# TRHCO2_datalogger.net
KiCad netlist of a schematic drawn in EAGLE
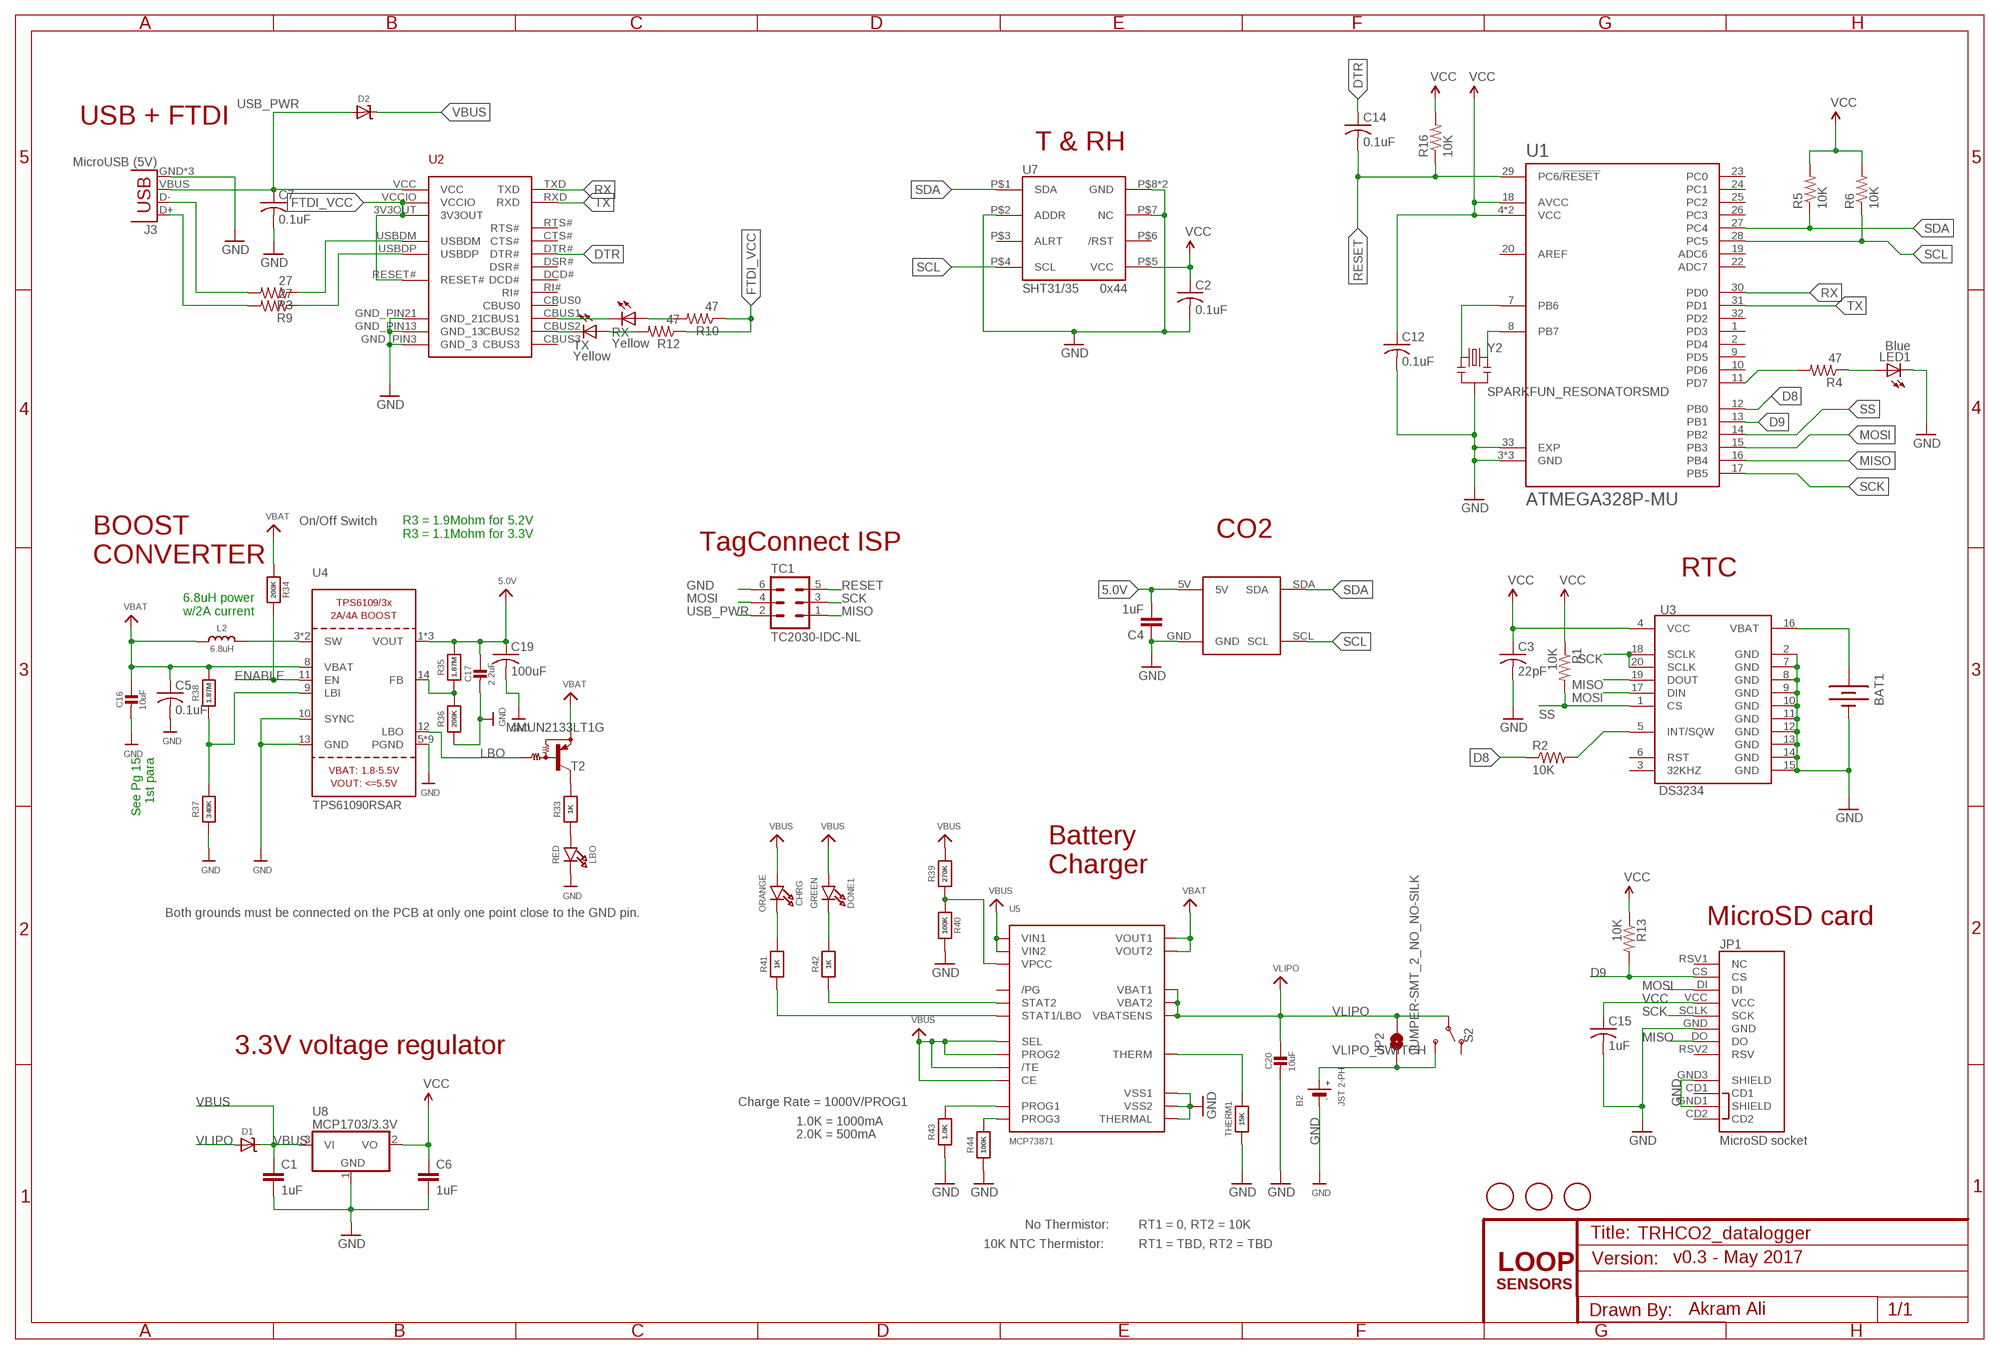
[diagram p0: schematic, sheet 1]

(export (version "E")
  (design (tool "Eeschema 10.0.6"))
  (components
    (comp (ref "B2")
      (value "JST 2-PH")
      (footprint "eagle-import:JSTPH2")
      (libsource (lib "eagle-import") (part "BATTERY"))
    )
    (comp (ref "BAT1")
      (value "BATTERY12MM")
      (footprint "eagle-import:BATTCON_12MM")
      (fields (field (name "MPN") "3000"))
      (libsource (lib "eagle-import") (part "BATTERY12MM"))
    )
    (comp (ref "C1")
      (value "1uF")
      (footprint "eagle-import:0805")
      (fields (field (name "MPN") "CC0805KKX7R7BB105"))
      (libsource (lib "eagle-import") (part "CAP0805"))
    )
    (comp (ref "C2")
      (value "0.1uF")
      (footprint "eagle-import:C0402")
      (libsource (lib "eagle-import") (part "C-USC0402"))
    )
    (comp (ref "C3")
      (value "22pF")
      (footprint "eagle-import:C0402")
      (libsource (lib "eagle-import") (part "C-USC0402"))
    )
    (comp (ref "C4")
      (value "1uF")
      (footprint "eagle-import:0805")
      (fields (field (name "MPN") "CC0805KKX7R7BB105"))
      (libsource (lib "eagle-import") (part "CAP0805"))
    )
    (comp (ref "C5")
      (value "0.1uF")
      (footprint "eagle-import:C0402")
      (libsource (lib "eagle-import") (part "C-USC0402"))
    )
    (comp (ref "C6")
      (value "1uF")
      (footprint "eagle-import:0805")
      (fields (field (name "MPN") "CC0805KKX7R7BB105"))
      (libsource (lib "eagle-import") (part "CAP0805"))
    )
    (comp (ref "C7")
      (value "0.1uF")
      (footprint "eagle-import:C0402")
      (libsource (lib "eagle-import") (part "C-USC0402"))
    )
    (comp (ref "C12")
      (value "0.1uF")
      (footprint "eagle-import:C0402")
      (libsource (lib "eagle-import") (part "C-USC0402"))
    )
    (comp (ref "C14")
      (value "0.1uF")
      (footprint "eagle-import:C0402")
      (libsource (lib "eagle-import") (part "C-USC0402"))
    )
    (comp (ref "C15")
      (value "1uF")
      (footprint "eagle-import:C0402")
      (libsource (lib "eagle-import") (part "C-USC0402"))
    )
    (comp (ref "C16")
      (value "10uF")
      (footprint "eagle-import:0805-NO")
      (libsource (lib "eagle-import") (part "CAP_CERAMIC0805-NOOUTLINE"))
    )
    (comp (ref "C17")
      (value "2.2uF")
      (footprint "eagle-import:0805-NO")
      (libsource (lib "eagle-import") (part "CAP_CERAMIC0805-NOOUTLINE"))
    )
    (comp (ref "C19")
      (value "100uF")
      (footprint "eagle-import:C1210")
      (libsource (lib "eagle-import") (part "rcl_334_C-USC1210"))
    )
    (comp (ref "C20")
      (value "10uF")
      (footprint "eagle-import:0805-NO")
      (libsource (lib "eagle-import") (part "CAP_CERAMIC0805-NOOUTLINE"))
    )
    (comp (ref "CHRG")
      (value "ORANGE")
      (footprint "eagle-import:CHIPLED_0805_NOOUTLINE")
      (libsource (lib "eagle-import") (part "LED0805_NOOUTLINE"))
    )
    (comp (ref "D1")
      (value "MICROBUILDER_DIODE-SCHOTTKYSOD-123")
      (footprint "eagle-import:MICROBUILDER_SOD-123")
      (libsource (lib "eagle-import") (part "MICROBUILDER_DIODE-SCHOTTKYSOD-123"))
    )
    (comp (ref "D2")
      (value "MICROBUILDER_DIODE-SCHOTTKYSOD-123")
      (footprint "eagle-import:MICROBUILDER_SOD-123")
      (libsource (lib "eagle-import") (part "MICROBUILDER_DIODE-SCHOTTKYSOD-123"))
    )
    (comp (ref "DONE1")
      (value "GREEN")
      (footprint "eagle-import:CHIPLED_0805_NOOUTLINE")
      (libsource (lib "eagle-import") (part "LED0805_NOOUTLINE"))
    )
    (comp (ref "J3")
      (value "MicroUSB (5V)")
      (footprint "eagle-import:USB-MICROB")
      (fields (field (name "MPN") "CONN-09505"))
      (libsource (lib "eagle-import") (part "USB-MICROB"))
    )
    (comp (ref "JP1")
      (value "MicroSD socket")
      (footprint "eagle-import:MICRO-SD-SOCKET-PP")
      (libsource (lib "eagle-import") (part "USD-SOCKETNEW"))
    )
    (comp (ref "JP2")
      (value "JUMPER-SMT_2_NO_NO-SILK")
      (footprint "eagle-import:SMT-JUMPER_2_NO_NO-SILK")
      (libsource (lib "eagle-import") (part "JUMPER-SMT_2_NO_NO-SILK"))
    )
    (comp (ref "L2")
      (value "6.8uH")
      (footprint "eagle-import:INDUCTOR_5X5MM_TDK_VLC5045")
      (libsource (lib "eagle-import") (part "INDUCTORTDK_VLC5045"))
    )
    (comp (ref "LBO")
      (value "RED")
      (footprint "eagle-import:CHIPLED_0805_NOOUTLINE")
      (libsource (lib "eagle-import") (part "LED0805_NOOUTLINE"))
    )
    (comp (ref "LED1")
      (value "Blue")
      (footprint "eagle-import:CHIPLED_0805")
      (fields (field (name "MPN") "150080BS75000"))
      (libsource (lib "eagle-import") (part "LEDCHIPLED_0805"))
    )
    (comp (ref "R1")
      (value "10K")
      (footprint "eagle-import:R0402")
      (libsource (lib "eagle-import") (part "R-US_R0402"))
    )
    (comp (ref "R2")
      (value "10K")
      (footprint "eagle-import:R0402")
      (libsource (lib "eagle-import") (part "R-US_R0402"))
    )
    (comp (ref "R3")
      (value "27")
      (footprint "eagle-import:R0402")
      (libsource (lib "eagle-import") (part "R-US_R0402"))
    )
    (comp (ref "R4")
      (value "47")
      (footprint "eagle-import:R0402")
      (libsource (lib "eagle-import") (part "R-US_R0402"))
    )
    (comp (ref "R5")
      (value "10K")
      (footprint "eagle-import:R0402")
      (libsource (lib "eagle-import") (part "R-US_R0402"))
    )
    (comp (ref "R6")
      (value "10K")
      (footprint "eagle-import:R0402")
      (libsource (lib "eagle-import") (part "R-US_R0402"))
    )
    (comp (ref "R9")
      (value "27")
      (footprint "eagle-import:R0402")
      (libsource (lib "eagle-import") (part "R-US_R0402"))
    )
    (comp (ref "R10")
      (value "47")
      (footprint "eagle-import:R0402")
      (libsource (lib "eagle-import") (part "R-US_R0402"))
    )
    (comp (ref "R12")
      (value "47")
      (footprint "eagle-import:R0402")
      (libsource (lib "eagle-import") (part "R-US_R0402"))
    )
    (comp (ref "R13")
      (value "10K")
      (footprint "eagle-import:R0402")
      (libsource (lib "eagle-import") (part "R-US_R0402"))
    )
    (comp (ref "R16")
      (value "10K")
      (footprint "eagle-import:R0402")
      (libsource (lib "eagle-import") (part "R-US_R0402"))
    )
    (comp (ref "R33")
      (value "1K")
      (footprint "eagle-import:0805-NO")
      (libsource (lib "eagle-import") (part "RESISTOR0805_NOOUTLINE"))
    )
    (comp (ref "R34")
      (value "200K")
      (footprint "eagle-import:0805-NO")
      (libsource (lib "eagle-import") (part "RESISTOR0805_NOOUTLINE"))
    )
    (comp (ref "R35")
      (value "1.87M")
      (footprint "eagle-import:0805-NO")
      (libsource (lib "eagle-import") (part "RESISTOR0805_NOOUTLINE"))
    )
    (comp (ref "R36")
      (value "200K")
      (footprint "eagle-import:0805-NO")
      (libsource (lib "eagle-import") (part "RESISTOR0805_NOOUTLINE"))
    )
    (comp (ref "R37")
      (value "340K")
      (footprint "eagle-import:_0805MP")
      (libsource (lib "eagle-import") (part "RESISTOR_0805MP"))
    )
    (comp (ref "R38")
      (value "1.87M")
      (footprint "eagle-import:_0805MP")
      (libsource (lib "eagle-import") (part "RESISTOR_0805MP"))
    )
    (comp (ref "R39")
      (value "270K")
      (footprint "eagle-import:0805-NO")
      (libsource (lib "eagle-import") (part "RESISTOR0805_NOOUTLINE"))
    )
    (comp (ref "R40")
      (value "100K")
      (footprint "eagle-import:0805-NO")
      (libsource (lib "eagle-import") (part "RESISTOR0805_NOOUTLINE"))
    )
    (comp (ref "R41")
      (value "1K")
      (footprint "eagle-import:0805-NO")
      (libsource (lib "eagle-import") (part "RESISTOR0805_NOOUTLINE"))
    )
    (comp (ref "R42")
      (value "1K")
      (footprint "eagle-import:0805-NO")
      (libsource (lib "eagle-import") (part "RESISTOR0805_NOOUTLINE"))
    )
    (comp (ref "R43")
      (value "1.0K")
      (footprint "eagle-import:0805-NO")
      (libsource (lib "eagle-import") (part "RESISTOR0805_NOOUTLINE"))
    )
    (comp (ref "R44")
      (value "100K")
      (footprint "eagle-import:0805-NO")
      (libsource (lib "eagle-import") (part "RESISTOR0805_NOOUTLINE"))
    )
    (comp (ref "RX")
      (value "Yellow")
      (footprint "eagle-import:CHIPLED_0805")
      (fields (field (name "MPN") "LG R971-KN-1"))
      (libsource (lib "eagle-import") (part "LEDCHIPLED_0805"))
    )
    (comp (ref "S2")
      (value "SWITCH-SPDT-SMD-RIGHT-ANGLE")
      (footprint "eagle-import:SWITCH_SPST_SMD_A")
      (libsource (lib "eagle-import") (part "SWITCH-SPDT-SMD-RIGHT-ANGLE"))
    )
    (comp (ref "T2")
      (value "MMUN2133LT1G")
      (footprint "eagle-import:SC59-BEC")
      (libsource (lib "eagle-import") (part "-PNP_DRIVER-SC59-BECMUN2114T1"))
    )
    (comp (ref "TC1")
      (value "TC2030-IDC-NL")
      (footprint "eagle-import:TC2030-IDC-NL")
      (libsource (lib "eagle-import") (part "TC2030-IDC-NL"))
    )
    (comp (ref "THERM1")
      (value "15K")
      (footprint "eagle-import:0805-NO")
      (libsource (lib "eagle-import") (part "RESISTOR0805_NOOUTLINE"))
    )
    (comp (ref "TX")
      (value "Yellow")
      (footprint "eagle-import:CHIPLED_0805")
      (fields (field (name "MPN") "LH R974-LP-1"))
      (libsource (lib "eagle-import") (part "LEDCHIPLED_0805"))
    )
    (comp (ref "U$1")
      (value "FIDUCIAL")
      (footprint "eagle-import:FIDUCIAL_1MM")
      (libsource (lib "eagle-import") (part "FIDUCIAL"))
    )
    (comp (ref "U$2")
      (value "FIDUCIAL")
      (footprint "eagle-import:FIDUCIAL_1MM")
      (libsource (lib "eagle-import") (part "FIDUCIAL"))
    )
    (comp (ref "U$3")
      (value "FIDUCIAL")
      (footprint "eagle-import:FIDUCIAL_1MM")
      (libsource (lib "eagle-import") (part "FIDUCIAL"))
    )
    (comp (ref "U1")
      (value "ATMEGA328P-MU")
      (footprint "eagle-import:QFN50P500X500X100-33N")
      (fields (field (name "MF") "Atmel"))
      (libsource (lib "eagle-import") (part "ATMEGA328P-MU"))
    )
    (comp (ref "U2")
      (value "FT231XQ-R")
      (footprint "eagle-import:FTDI_FT231XQ-R_PACKAGE")
      (libsource (lib "eagle-import") (part "FT231XQ-R"))
    )
    (comp (ref "U3")
      (value "DS3234")
      (footprint "eagle-import:DS3234")
      (fields (field (name "MPN") "DS3234S#"))
      (libsource (lib "eagle-import") (part "DS3234"))
    )
    (comp (ref "U4")
      (value "TPS61090RSAR")
      (footprint "eagle-import:PVQFN-16")
      (libsource (lib "eagle-import") (part "VREG_TPS6103X"))
    )
    (comp (ref "U5")
      (value "MCP73871")
      (footprint "eagle-import:QFN20_4MM")
      (libsource (lib "eagle-import") (part "MCP73871"))
    )
    (comp (ref "U6")
      (value "K30-CO2-I2C")
      (footprint "eagle-import:K30-CO2-I2C")
      (libsource (lib "eagle-import") (part "K30-CO2-I2C"))
    )
    (comp (ref "U7")
      (value "SHT31/35")
      (footprint "eagle-import:SHT3X")
      (fields (field (name "MPN") "SHT31-DIS-B"))
      (libsource (lib "eagle-import") (part "SHT31-DIS"))
    )
    (comp (ref "U8")
      (value "MCP1703/3.3V")
      (footprint "eagle-import:SOT23")
      (fields (field (name "MPN") "MCP1703T-2502E/CB"))
      (libsource (lib "eagle-import") (part "MCP1703CB"))
    )
    (comp (ref "Y2")
      (value "SPARKFUN_RESONATORSMD")
      (footprint "eagle-import:SPARKFUN_RESONATOR-SMD")
      (libsource (lib "eagle-import") (part "SPARKFUN_RESONATORSMD"))
    )
  )
  (nets
    (net (code "1") (name "/ENABLE") (class "Default")
      (node (ref "R34") (pin "2") (pinfunction "2_2") (pintype "passive"))
      (node (ref "U4") (pin "11") (pinfunction "EN_11") (pintype "input"))
    )
    (net (code "2") (name "/LBO") (class "Default")
      (node (ref "T2") (pin "B") (pinfunction "B_B") (pintype "passive"))
      (node (ref "U4") (pin "12") (pinfunction "LBO_12") (pintype "output"))
    )
    (net (code "3") (name "/USB_PWR") (class "Default")
      (node (ref "C7") (pin "1") (pinfunction "1_1") (pintype "passive"))
      (node (ref "D2") (pin "A") (pinfunction "A_A") (pintype "passive"))
      (node (ref "J3") (pin "VBUS") (pinfunction "VBUS_VBUS") (pintype "bidirectional"))
      (node (ref "TC1") (pin "2") (pinfunction "2_2") (pintype "passive"))
      (node (ref "U2") (pin "VCC") (pinfunction "VCC_VCC") (pintype "bidirectional"))
    )
    (net (code "4") (name "/VLIPO_SWITCH") (class "Default")
      (node (ref "B2") (pin "2") (pinfunction "+_2") (pintype "passive"))
      (node (ref "JP2") (pin "1") (pinfunction "1_1") (pintype "passive"))
      (node (ref "S2") (pin "3") (pinfunction "S_3") (pintype "passive"))
    )
    (net (code "5") (name "5.0V") (class "Default")
      (node (ref "C17") (pin "1") (pinfunction "1_1") (pintype "passive"))
      (node (ref "C19") (pin "1") (pinfunction "1_1") (pintype "passive"))
      (node (ref "C4") (pin "2") (pinfunction "2_2") (pintype "passive"))
      (node (ref "R35") (pin "2") (pinfunction "2_2") (pintype "passive"))
      (node (ref "U4") (pin "1") (pinfunction "VOUT_1") (pintype "power_in"))
      (node (ref "U4") (pin "15") (pinfunction "VOUT_15") (pintype "power_in"))
      (node (ref "U4") (pin "16") (pinfunction "VOUT_16") (pintype "power_in"))
      (node (ref "U6") (pin "5V") (pinfunction "5V_5V") (pintype "bidirectional"))
    )
    (net (code "6") (name "D8") (class "Default")
      (node (ref "R2") (pin "1") (pinfunction "1_1") (pintype "passive"))
      (node (ref "U1") (pin "12") (pinfunction "PB0_12") (pintype "bidirectional"))
    )
    (net (code "7") (name "D9") (class "Default")
      (node (ref "JP1") (pin "CS") (pinfunction "CS_CS") (pintype "bidirectional"))
      (node (ref "R13") (pin "2") (pinfunction "2_2") (pintype "passive"))
      (node (ref "U1") (pin "13") (pinfunction "PB1_13") (pintype "bidirectional"))
    )
    (net (code "8") (name "DTR") (class "Default")
      (node (ref "C14") (pin "1") (pinfunction "1_1") (pintype "passive"))
      (node (ref "U2") (pin "DTR#") (pinfunction "DTR#_DTR#") (pintype "bidirectional"))
    )
    (net (code "9") (name "FTDI_VCC") (class "Default")
      (node (ref "R10") (pin "1") (pinfunction "1_1") (pintype "passive"))
      (node (ref "R12") (pin "1") (pinfunction "1_1") (pintype "passive"))
      (node (ref "U2") (pin "3V3OUT") (pinfunction "3V3OUT_3V3OUT") (pintype "bidirectional"))
      (node (ref "U2") (pin "RESET#") (pinfunction "RESET#_RESET#") (pintype "bidirectional"))
      (node (ref "U2") (pin "VCCIO") (pinfunction "VCCIO_VCCIO") (pintype "bidirectional"))
    )
    (net (code "10") (name "GND") (class "Default")
      (node (ref "B2") (pin "1") (pinfunction "-_1") (pintype "passive"))
      (node (ref "BAT1") (pin "GND") (pinfunction "-_GND") (pintype "power_in"))
      (node (ref "C1") (pin "2") (pinfunction "2_2") (pintype "passive"))
      (node (ref "C12") (pin "2") (pinfunction "2_2") (pintype "passive"))
      (node (ref "C15") (pin "2") (pinfunction "2_2") (pintype "passive"))
      (node (ref "C16") (pin "2") (pinfunction "2_2") (pintype "passive"))
      (node (ref "C17") (pin "2") (pinfunction "2_2") (pintype "passive"))
      (node (ref "C19") (pin "2") (pinfunction "2_2") (pintype "passive"))
      (node (ref "C2") (pin "2") (pinfunction "2_2") (pintype "passive"))
      (node (ref "C20") (pin "2") (pinfunction "2_2") (pintype "passive"))
      (node (ref "C3") (pin "2") (pinfunction "2_2") (pintype "passive"))
      (node (ref "C4") (pin "1") (pinfunction "1_1") (pintype "passive"))
      (node (ref "C5") (pin "2") (pinfunction "2_2") (pintype "passive"))
      (node (ref "C6") (pin "2") (pinfunction "2_2") (pintype "passive"))
      (node (ref "C7") (pin "2") (pinfunction "2_2") (pintype "passive"))
      (node (ref "J3") (pin "GND") (pinfunction "GND_GND") (pintype "bidirectional"))
      (node (ref "J3") (pin "MT1") (pinfunction "GND_MT1") (pintype "bidirectional"))
      (node (ref "J3") (pin "MT2") (pinfunction "GND_MT2") (pintype "bidirectional"))
      (node (ref "JP1") (pin "GND") (pinfunction "GND_GND") (pintype "bidirectional"))
      (node (ref "JP1") (pin "GND1") (pinfunction "SHIELD_GND1") (pintype "bidirectional"))
      (node (ref "JP1") (pin "GND3") (pinfunction "SHIELD_GND3") (pintype "bidirectional"))
      (node (ref "LBO") (pin "C") (pinfunction "C_C") (pintype "passive"))
      (node (ref "LED1") (pin "C") (pinfunction "C_C") (pintype "passive"))
      (node (ref "R36") (pin "1") (pinfunction "1_1") (pintype "passive"))
      (node (ref "R37") (pin "1") (pinfunction "1_1") (pintype "passive"))
      (node (ref "R40") (pin "2") (pinfunction "2_2") (pintype "passive"))
      (node (ref "R43") (pin "1") (pinfunction "1_1") (pintype "passive"))
      (node (ref "R44") (pin "1") (pinfunction "1_1") (pintype "passive"))
      (node (ref "TC1") (pin "6") (pinfunction "6_6") (pintype "passive"))
      (node (ref "THERM1") (pin "1") (pinfunction "1_1") (pintype "passive"))
      (node (ref "U1") (pin "21") (pinfunction "GND_21") (pintype "power_in"))
      (node (ref "U1") (pin "3") (pinfunction "GND_3") (pintype "power_in"))
      (node (ref "U1") (pin "33") (pinfunction "EXP_33") (pintype "power_in"))
      (node (ref "U1") (pin "5") (pinfunction "GND_5") (pintype "power_in"))
      (node (ref "U2") (pin "GND_PIN13") (pinfunction "GND_13_GND_PIN13") (pintype "bidirectional"))
      (node (ref "U2") (pin "GND_PIN21") (pinfunction "GND_21_GND_PIN21") (pintype "bidirectional"))
      (node (ref "U2") (pin "GND_PIN3") (pinfunction "GND_3_GND_PIN3") (pintype "bidirectional"))
      (node (ref "U3") (pin "10") (pinfunction "GND_10") (pintype "bidirectional"))
      (node (ref "U3") (pin "11") (pinfunction "GND_11") (pintype "bidirectional"))
      (node (ref "U3") (pin "12") (pinfunction "GND_12") (pintype "bidirectional"))
      (node (ref "U3") (pin "13") (pinfunction "GND_13") (pintype "bidirectional"))
      (node (ref "U3") (pin "14") (pinfunction "GND_14") (pintype "bidirectional"))
      (node (ref "U3") (pin "15") (pinfunction "GND_15") (pintype "bidirectional"))
      (node (ref "U3") (pin "2") (pinfunction "GND_2") (pintype "bidirectional"))
      (node (ref "U3") (pin "7") (pinfunction "GND_7") (pintype "bidirectional"))
      (node (ref "U3") (pin "8") (pinfunction "GND_8") (pintype "bidirectional"))
      (node (ref "U3") (pin "9") (pinfunction "GND_9") (pintype "bidirectional"))
      (node (ref "U4") (pin "10") (pinfunction "SYNC_10") (pintype "input"))
      (node (ref "U4") (pin "13") (pinfunction "GND_13") (pintype "power_in"))
      (node (ref "U4") (pin "5") (pinfunction "PGND_5") (pintype "power_in"))
      (node (ref "U4") (pin "6") (pinfunction "PGND_6") (pintype "power_in"))
      (node (ref "U4") (pin "7") (pinfunction "PGND_7") (pintype "power_in"))
      (node (ref "U4") (pin "P$18") (pinfunction "PGND_P$18") (pintype "power_in"))
      (node (ref "U4") (pin "P$19") (pinfunction "PGND_P$19") (pintype "power_in"))
      (node (ref "U4") (pin "P$20") (pinfunction "PGND_P$20") (pintype "power_in"))
      (node (ref "U4") (pin "P$21") (pinfunction "PGND_P$21") (pintype "power_in"))
      (node (ref "U4") (pin "P$22") (pinfunction "PGND_P$22") (pintype "power_in"))
      (node (ref "U4") (pin "THERMAL") (pinfunction "PGND_THERMAL") (pintype "power_in"))
      (node (ref "U5") (pin "P$10") (pinfunction "VSS1_P$10") (pintype "bidirectional"))
      (node (ref "U5") (pin "P$11") (pinfunction "VSS2_P$11") (pintype "bidirectional"))
      (node (ref "U5") (pin "P$21") (pinfunction "THERMAL_P$21") (pintype "bidirectional"))
      (node (ref "U6") (pin "GND") (pinfunction "GND_GND") (pintype "bidirectional"))
      (node (ref "U7") (pin "P$2") (pinfunction "ADDR_P$2") (pintype "bidirectional"))
      (node (ref "U7") (pin "P$7") (pinfunction "NC_P$7") (pintype "bidirectional"))
      (node (ref "U7") (pin "P$8") (pinfunction "GND_P$8") (pintype "bidirectional"))
      (node (ref "U7") (pin "PAD") (pinfunction "GND_PAD") (pintype "bidirectional"))
      (node (ref "U8") (pin "1") (pinfunction "GND_1") (pintype "passive"))
      (node (ref "Y2") (pin "2") (pinfunction "2_2") (pintype "passive"))
    )
    (net (code "11") (name "MISO") (class "Default")
      (node (ref "JP1") (pin "DO") (pinfunction "DO_DO") (pintype "bidirectional"))
      (node (ref "TC1") (pin "1") (pinfunction "1_1") (pintype "passive"))
      (node (ref "U1") (pin "16") (pinfunction "PB4_16") (pintype "bidirectional"))
      (node (ref "U3") (pin "19") (pinfunction "DOUT_19") (pintype "bidirectional"))
    )
    (net (code "12") (name "MOSI") (class "Default")
      (node (ref "JP1") (pin "DI") (pinfunction "DI_DI") (pintype "bidirectional"))
      (node (ref "TC1") (pin "4") (pinfunction "4_4") (pintype "passive"))
      (node (ref "U1") (pin "15") (pinfunction "PB3_15") (pintype "bidirectional"))
      (node (ref "U3") (pin "17") (pinfunction "DIN_17") (pintype "bidirectional"))
    )
    (net (code "13") (name "Net-(BAT1-+)") (class "Default")
      (node (ref "BAT1") (pin "PWR@1") (pinfunction "+_PWR@1") (pintype "power_in"))
      (node (ref "U3") (pin "16") (pinfunction "VBAT_16") (pintype "bidirectional"))
    )
    (net (code "14") (name "Net-(CHRG-PadC)") (class "Default")
      (node (ref "CHRG") (pin "C") (pinfunction "C_C") (pintype "passive"))
      (node (ref "R41") (pin "2") (pinfunction "2_2") (pintype "passive"))
    )
    (net (code "15") (name "Net-(DONE1-PadC)") (class "Default")
      (node (ref "DONE1") (pin "C") (pinfunction "C_C") (pintype "passive"))
      (node (ref "R42") (pin "2") (pinfunction "2_2") (pintype "passive"))
    )
    (net (code "16") (name "Net-(J3-PadD+)") (class "Default")
      (node (ref "J3") (pin "D+") (pinfunction "D+_D+") (pintype "bidirectional"))
      (node (ref "R9") (pin "2") (pinfunction "2_2") (pintype "passive"))
    )
    (net (code "17") (name "Net-(J3-PadD-)") (class "Default")
      (node (ref "J3") (pin "D-") (pinfunction "D-_D-") (pintype "bidirectional"))
      (node (ref "R3") (pin "2") (pinfunction "2_2") (pintype "passive"))
    )
    (net (code "18") (name "Net-(L2-2)") (class "Default")
      (node (ref "L2") (pin "P$2") (pinfunction "2_P$2") (pintype "passive"))
      (node (ref "U4") (pin "3") (pinfunction "SW_3") (pintype "input"))
      (node (ref "U4") (pin "4") (pinfunction "SW_4") (pintype "input"))
    )
    (net (code "19") (name "Net-(LBO-PadA)") (class "Default")
      (node (ref "LBO") (pin "A") (pinfunction "A_A") (pintype "passive"))
      (node (ref "R33") (pin "1") (pinfunction "1_1") (pintype "passive"))
    )
    (net (code "20") (name "Net-(LED1-PadA)") (class "Default")
      (node (ref "LED1") (pin "A") (pinfunction "A_A") (pintype "passive"))
      (node (ref "R4") (pin "1") (pinfunction "1_1") (pintype "passive"))
    )
    (net (code "21") (name "Net-(R3-Pad1)") (class "Default")
      (node (ref "R3") (pin "1") (pinfunction "1_1") (pintype "passive"))
      (node (ref "U2") (pin "USBDM") (pinfunction "USBDM_USBDM") (pintype "bidirectional"))
    )
    (net (code "22") (name "Net-(R9-Pad1)") (class "Default")
      (node (ref "R9") (pin "1") (pinfunction "1_1") (pintype "passive"))
      (node (ref "U2") (pin "USBDP") (pinfunction "USBDP_USBDP") (pintype "bidirectional"))
    )
    (net (code "23") (name "Net-(R10-Pad2)") (class "Default")
      (node (ref "R10") (pin "2") (pinfunction "2_2") (pintype "passive"))
      (node (ref "RX") (pin "A") (pinfunction "A_A") (pintype "passive"))
    )
    (net (code "24") (name "Net-(R12-Pad2)") (class "Default")
      (node (ref "R12") (pin "2") (pinfunction "2_2") (pintype "passive"))
      (node (ref "TX") (pin "A") (pinfunction "A_A") (pintype "passive"))
    )
    (net (code "25") (name "Net-(R33-Pad2)") (class "Default")
      (node (ref "R33") (pin "2") (pinfunction "2_2") (pintype "passive"))
      (node (ref "T2") (pin "C") (pinfunction "C_C") (pintype "passive"))
    )
    (net (code "26") (name "Net-(RX-PadC)") (class "Default")
      (node (ref "RX") (pin "C") (pinfunction "C_C") (pintype "passive"))
      (node (ref "U2") (pin "CBUS1") (pinfunction "CBUS1_CBUS1") (pintype "bidirectional"))
    )
    (net (code "27") (name "Net-(TX-PadC)") (class "Default")
      (node (ref "TX") (pin "C") (pinfunction "C_C") (pintype "passive"))
      (node (ref "U2") (pin "CBUS2") (pinfunction "CBUS2_CBUS2") (pintype "bidirectional"))
    )
    (net (code "28") (name "Net-(U1-PB6)") (class "Default")
      (node (ref "U1") (pin "7") (pinfunction "PB6_7") (pintype "bidirectional"))
      (node (ref "Y2") (pin "1") (pinfunction "1_1") (pintype "passive"))
    )
    (net (code "29") (name "Net-(U1-PB7)") (class "Default")
      (node (ref "U1") (pin "8") (pinfunction "PB7_8") (pintype "bidirectional"))
      (node (ref "Y2") (pin "3") (pinfunction "3_3") (pintype "passive"))
    )
    (net (code "30") (name "Net-(U1-PD7)") (class "Default")
      (node (ref "R4") (pin "2") (pinfunction "2_2") (pintype "passive"))
      (node (ref "U1") (pin "11") (pinfunction "PD7_11") (pintype "bidirectional"))
    )
    (net (code "31") (name "Net-(U3-INT{slash}SQW)") (class "Default")
      (node (ref "R2") (pin "2") (pinfunction "2_2") (pintype "passive"))
      (node (ref "U3") (pin "5") (pinfunction "INT/SQW_5") (pintype "bidirectional"))
    )
    (net (code "32") (name "Net-(U4-FB)") (class "Default")
      (node (ref "R35") (pin "1") (pinfunction "1_1") (pintype "passive"))
      (node (ref "R36") (pin "2") (pinfunction "2_2") (pintype "passive"))
      (node (ref "U4") (pin "14") (pinfunction "FB_14") (pintype "input"))
    )
    (net (code "33") (name "Net-(U4-LBI)") (class "Default")
      (node (ref "R37") (pin "2") (pinfunction "2_2") (pintype "passive"))
      (node (ref "R38") (pin "1") (pinfunction "1_1") (pintype "passive"))
      (node (ref "U4") (pin "9") (pinfunction "LBI_9") (pintype "input"))
    )
    (net (code "34") (name "Net-(U5-PROG1)") (class "Default")
      (node (ref "R43") (pin "2") (pinfunction "2_2") (pintype "passive"))
      (node (ref "U5") (pin "P$13") (pinfunction "PROG1_P$13") (pintype "bidirectional"))
    )
    (net (code "35") (name "Net-(U5-PROG3)") (class "Default")
      (node (ref "R44") (pin "2") (pinfunction "2_2") (pintype "passive"))
      (node (ref "U5") (pin "P$12") (pinfunction "PROG3_P$12") (pintype "bidirectional"))
    )
    (net (code "36") (name "Net-(U5-STAT1{slash}LBO)") (class "Default")
      (node (ref "R41") (pin "1") (pinfunction "1_1") (pintype "passive"))
      (node (ref "U5") (pin "P$8") (pinfunction "STAT1/LBO_P$8") (pintype "bidirectional"))
    )
    (net (code "37") (name "Net-(U5-STAT2)") (class "Default")
      (node (ref "R42") (pin "1") (pinfunction "1_1") (pintype "passive"))
      (node (ref "U5") (pin "P$7") (pinfunction "STAT2_P$7") (pintype "bidirectional"))
    )
    (net (code "38") (name "Net-(U5-THERM)") (class "Default")
      (node (ref "THERM1") (pin "2") (pinfunction "2_2") (pintype "passive"))
      (node (ref "U5") (pin "P$5") (pinfunction "THERM_P$5") (pintype "bidirectional"))
    )
    (net (code "39") (name "Net-(U5-VPCC)") (class "Default")
      (node (ref "R39") (pin "1") (pinfunction "1_1") (pintype "passive"))
      (node (ref "R40") (pin "1") (pinfunction "1_1") (pintype "passive"))
      (node (ref "U5") (pin "P$2") (pinfunction "VPCC_P$2") (pintype "bidirectional"))
    )
    (net (code "40") (name "RESET") (class "Default")
      (node (ref "C14") (pin "2") (pinfunction "2_2") (pintype "passive"))
      (node (ref "R16") (pin "1") (pinfunction "1_1") (pintype "passive"))
      (node (ref "TC1") (pin "5") (pinfunction "5_5") (pintype "passive"))
      (node (ref "U1") (pin "29") (pinfunction "PC6/~{RESET}_29") (pintype "bidirectional"))
    )
    (net (code "41") (name "RX") (class "Default")
      (node (ref "U1") (pin "30") (pinfunction "PD0_30") (pintype "bidirectional"))
      (node (ref "U2") (pin "TXD") (pinfunction "TXD_TXD") (pintype "bidirectional"))
    )
    (net (code "42") (name "SCK") (class "Default")
      (node (ref "JP1") (pin "SCLK") (pinfunction "SCK_SCLK") (pintype "bidirectional"))
      (node (ref "TC1") (pin "3") (pinfunction "3_3") (pintype "passive"))
      (node (ref "U1") (pin "17") (pinfunction "PB5_17") (pintype "bidirectional"))
      (node (ref "U3") (pin "18") (pinfunction "SCLK_18") (pintype "bidirectional"))
      (node (ref "U3") (pin "20") (pinfunction "SCLK_20") (pintype "bidirectional"))
    )
    (net (code "43") (name "SCL") (class "Default")
      (node (ref "R6") (pin "1") (pinfunction "1_1") (pintype "passive"))
      (node (ref "U1") (pin "28") (pinfunction "PC5_28") (pintype "bidirectional"))
      (node (ref "U6") (pin "SCL") (pinfunction "SCL_SCL") (pintype "bidirectional"))
      (node (ref "U7") (pin "P$4") (pinfunction "SCL_P$4") (pintype "bidirectional"))
    )
    (net (code "44") (name "SDA") (class "Default")
      (node (ref "R5") (pin "1") (pinfunction "1_1") (pintype "passive"))
      (node (ref "U1") (pin "27") (pinfunction "PC4_27") (pintype "bidirectional"))
      (node (ref "U6") (pin "SDA") (pinfunction "SDA_SDA") (pintype "bidirectional"))
      (node (ref "U7") (pin "P$1") (pinfunction "SDA_P$1") (pintype "bidirectional"))
    )
    (net (code "45") (name "SS") (class "Default")
      (node (ref "R1") (pin "2") (pinfunction "2_2") (pintype "passive"))
      (node (ref "U1") (pin "14") (pinfunction "PB2_14") (pintype "bidirectional"))
      (node (ref "U3") (pin "1") (pinfunction "CS_1") (pintype "bidirectional"))
    )
    (net (code "46") (name "TX") (class "Default")
      (node (ref "U1") (pin "31") (pinfunction "PD1_31") (pintype "bidirectional"))
      (node (ref "U2") (pin "RXD") (pinfunction "RXD_RXD") (pintype "bidirectional"))
    )
    (net (code "47") (name "VBAT") (class "Default")
      (node (ref "C16") (pin "1") (pinfunction "1_1") (pintype "passive"))
      (node (ref "C5") (pin "1") (pinfunction "1_1") (pintype "passive"))
      (node (ref "L2") (pin "P$1") (pinfunction "1_P$1") (pintype "passive"))
      (node (ref "R34") (pin "1") (pinfunction "1_1") (pintype "passive"))
      (node (ref "R38") (pin "2") (pinfunction "2_2") (pintype "passive"))
      (node (ref "T2") (pin "E") (pinfunction "E_E") (pintype "passive"))
      (node (ref "U4") (pin "8") (pinfunction "VBAT_8") (pintype "input"))
      (node (ref "U5") (pin "P$1") (pinfunction "VOUT1_P$1") (pintype "bidirectional"))
      (node (ref "U5") (pin "P$20") (pinfunction "VOUT2_P$20") (pintype "bidirectional"))
    )
    (net (code "48") (name "VBUS") (class "Default")
      (node (ref "C1") (pin "1") (pinfunction "1_1") (pintype "passive"))
      (node (ref "CHRG") (pin "A") (pinfunction "A_A") (pintype "passive"))
      (node (ref "D1") (pin "C") (pinfunction "C_C") (pintype "passive"))
      (node (ref "D2") (pin "C") (pinfunction "C_C") (pintype "passive"))
      (node (ref "DONE1") (pin "A") (pinfunction "A_A") (pintype "passive"))
      (node (ref "R39") (pin "2") (pinfunction "2_2") (pintype "passive"))
      (node (ref "U5") (pin "P$17") (pinfunction "CE_P$17") (pintype "bidirectional"))
      (node (ref "U5") (pin "P$18") (pinfunction "VIN1_P$18") (pintype "bidirectional"))
      (node (ref "U5") (pin "P$19") (pinfunction "VIN2_P$19") (pintype "bidirectional"))
      (node (ref "U5") (pin "P$3") (pinfunction "SEL_P$3") (pintype "bidirectional"))
      (node (ref "U5") (pin "P$4") (pinfunction "PROG2_P$4") (pintype "bidirectional"))
      (node (ref "U5") (pin "P$9") (pinfunction "/TE_P$9") (pintype "bidirectional"))
      (node (ref "U8") (pin "3") (pinfunction "VI_3") (pintype "input"))
    )
    (net (code "49") (name "VCC") (class "Default")
      (node (ref "C12") (pin "1") (pinfunction "1_1") (pintype "passive"))
      (node (ref "C15") (pin "1") (pinfunction "1_1") (pintype "passive"))
      (node (ref "C2") (pin "1") (pinfunction "1_1") (pintype "passive"))
      (node (ref "C3") (pin "1") (pinfunction "1_1") (pintype "passive"))
      (node (ref "C6") (pin "1") (pinfunction "1_1") (pintype "passive"))
      (node (ref "JP1") (pin "VCC") (pinfunction "VCC_VCC") (pintype "bidirectional"))
      (node (ref "R1") (pin "1") (pinfunction "1_1") (pintype "passive"))
      (node (ref "R13") (pin "1") (pinfunction "1_1") (pintype "passive"))
      (node (ref "R16") (pin "2") (pinfunction "2_2") (pintype "passive"))
      (node (ref "R5") (pin "2") (pinfunction "2_2") (pintype "passive"))
      (node (ref "R6") (pin "2") (pinfunction "2_2") (pintype "passive"))
      (node (ref "U1") (pin "18") (pinfunction "AVCC_18") (pintype "power_in"))
      (node (ref "U1") (pin "4") (pinfunction "VCC_4") (pintype "power_in"))
      (node (ref "U1") (pin "6") (pinfunction "VCC_6") (pintype "power_in"))
      (node (ref "U3") (pin "4") (pinfunction "VCC_4") (pintype "bidirectional"))
      (node (ref "U7") (pin "P$5") (pinfunction "VCC_P$5") (pintype "bidirectional"))
      (node (ref "U8") (pin "2") (pinfunction "VO_2") (pintype "passive"))
    )
    (net (code "50") (name "VLIPO") (class "Default")
      (node (ref "C20") (pin "1") (pinfunction "1_1") (pintype "passive"))
      (node (ref "D1") (pin "A") (pinfunction "A_A") (pintype "passive"))
      (node (ref "JP2") (pin "2") (pinfunction "2_2") (pintype "passive"))
      (node (ref "S2") (pin "2") (pinfunction "P_2") (pintype "passive"))
      (node (ref "U5") (pin "P$14") (pinfunction "VBAT1_P$14") (pintype "bidirectional"))
      (node (ref "U5") (pin "P$15") (pinfunction "VBAT2_P$15") (pintype "bidirectional"))
      (node (ref "U5") (pin "P$16") (pinfunction "VBATSENS_P$16") (pintype "bidirectional"))
    )
    (net (code "51") (name "unconnected-(JP1-NC-PadRSV1)") (class "Default")
      (node (ref "JP1") (pin "RSV1") (pinfunction "NC_RSV1") (pintype "bidirectional"))
    )
    (net (code "52") (name "unconnected-(JP1-PadCD1)") (class "Default")
      (node (ref "JP1") (pin "CD1") (pinfunction "CD1_CD1") (pintype "bidirectional"))
    )
    (net (code "53") (name "unconnected-(JP1-PadCD2)") (class "Default")
      (node (ref "JP1") (pin "CD2") (pinfunction "CD2_CD2") (pintype "bidirectional"))
    )
    (net (code "54") (name "unconnected-(JP1-RSV-PadRSV2)") (class "Default")
      (node (ref "JP1") (pin "RSV2") (pinfunction "RSV_RSV2") (pintype "bidirectional"))
    )
    (net (code "55") (name "unconnected-(S2-O-Pad1)") (class "Default")
      (node (ref "S2") (pin "1") (pinfunction "O_1") (pintype "passive"))
    )
    (net (code "56") (name "unconnected-(U1-ADC6-Pad19)") (class "Default")
      (node (ref "U1") (pin "19") (pinfunction "ADC6_19") (pintype "bidirectional"))
    )
    (net (code "57") (name "unconnected-(U1-ADC7-Pad22)") (class "Default")
      (node (ref "U1") (pin "22") (pinfunction "ADC7_22") (pintype "bidirectional"))
    )
    (net (code "58") (name "unconnected-(U1-AREF-Pad20)") (class "Default")
      (node (ref "U1") (pin "20") (pinfunction "AREF_20") (pintype "input"))
    )
    (net (code "59") (name "unconnected-(U1-PC0-Pad23)") (class "Default")
      (node (ref "U1") (pin "23") (pinfunction "PC0_23") (pintype "bidirectional"))
    )
    (net (code "60") (name "unconnected-(U1-PC1-Pad24)") (class "Default")
      (node (ref "U1") (pin "24") (pinfunction "PC1_24") (pintype "bidirectional"))
    )
    (net (code "61") (name "unconnected-(U1-PC2-Pad25)") (class "Default")
      (node (ref "U1") (pin "25") (pinfunction "PC2_25") (pintype "bidirectional"))
    )
    (net (code "62") (name "unconnected-(U1-PC3-Pad26)") (class "Default")
      (node (ref "U1") (pin "26") (pinfunction "PC3_26") (pintype "bidirectional"))
    )
    (net (code "63") (name "unconnected-(U1-PD2-Pad32)") (class "Default")
      (node (ref "U1") (pin "32") (pinfunction "PD2_32") (pintype "bidirectional"))
    )
    (net (code "64") (name "unconnected-(U1-PD3-Pad1)") (class "Default")
      (node (ref "U1") (pin "1") (pinfunction "PD3_1") (pintype "bidirectional"))
    )
    (net (code "65") (name "unconnected-(U1-PD4-Pad2)") (class "Default")
      (node (ref "U1") (pin "2") (pinfunction "PD4_2") (pintype "bidirectional"))
    )
    (net (code "66") (name "unconnected-(U1-PD5-Pad9)") (class "Default")
      (node (ref "U1") (pin "9") (pinfunction "PD5_9") (pintype "bidirectional"))
    )
    (net (code "67") (name "unconnected-(U1-PD6-Pad10)") (class "Default")
      (node (ref "U1") (pin "10") (pinfunction "PD6_10") (pintype "bidirectional"))
    )
    (net (code "68") (name "unconnected-(U2-PadCBUS0)") (class "Default")
      (node (ref "U2") (pin "CBUS0") (pinfunction "CBUS0_CBUS0") (pintype "bidirectional"))
    )
    (net (code "69") (name "unconnected-(U2-PadCBUS3)") (class "Default")
      (node (ref "U2") (pin "CBUS3") (pinfunction "CBUS3_CBUS3") (pintype "bidirectional"))
    )
    (net (code "70") (name "unconnected-(U2-PadCTS#)") (class "Default")
      (node (ref "U2") (pin "CTS#") (pinfunction "CTS#_CTS#") (pintype "bidirectional"))
    )
    (net (code "71") (name "unconnected-(U2-PadDCD#)") (class "Default")
      (node (ref "U2") (pin "DCD#") (pinfunction "DCD#_DCD#") (pintype "bidirectional"))
    )
    (net (code "72") (name "unconnected-(U2-PadDSR#)") (class "Default")
      (node (ref "U2") (pin "DSR#") (pinfunction "DSR#_DSR#") (pintype "bidirectional"))
    )
    (net (code "73") (name "unconnected-(U2-PadRI#)") (class "Default")
      (node (ref "U2") (pin "RI#") (pinfunction "RI#_RI#") (pintype "bidirectional"))
    )
    (net (code "74") (name "unconnected-(U2-PadRTS#)") (class "Default")
      (node (ref "U2") (pin "RTS#") (pinfunction "RTS#_RTS#") (pintype "bidirectional"))
    )
    (net (code "75") (name "unconnected-(U3-32KHZ-Pad3)") (class "Default")
      (node (ref "U3") (pin "3") (pinfunction "32KHZ_3") (pintype "bidirectional"))
    )
    (net (code "76") (name "unconnected-(U3-RST-Pad6)") (class "Default")
      (node (ref "U3") (pin "6") (pinfunction "RST_6") (pintype "bidirectional"))
    )
    (net (code "77") (name "unconnected-(U5-{slash}PG-PadP$6)") (class "Default")
      (node (ref "U5") (pin "P$6") (pinfunction "/PG_P$6") (pintype "bidirectional"))
    )
    (net (code "78") (name "unconnected-(U7-ALRT-PadP$3)") (class "Default")
      (node (ref "U7") (pin "P$3") (pinfunction "ALRT_P$3") (pintype "bidirectional"))
    )
    (net (code "79") (name "unconnected-(U7-{slash}RST-PadP$6)") (class "Default")
      (node (ref "U7") (pin "P$6") (pinfunction "/RST_P$6") (pintype "bidirectional"))
    )
  )
)
